# circuit.net
KiCad netlist of a schematic drawn in EAGLE
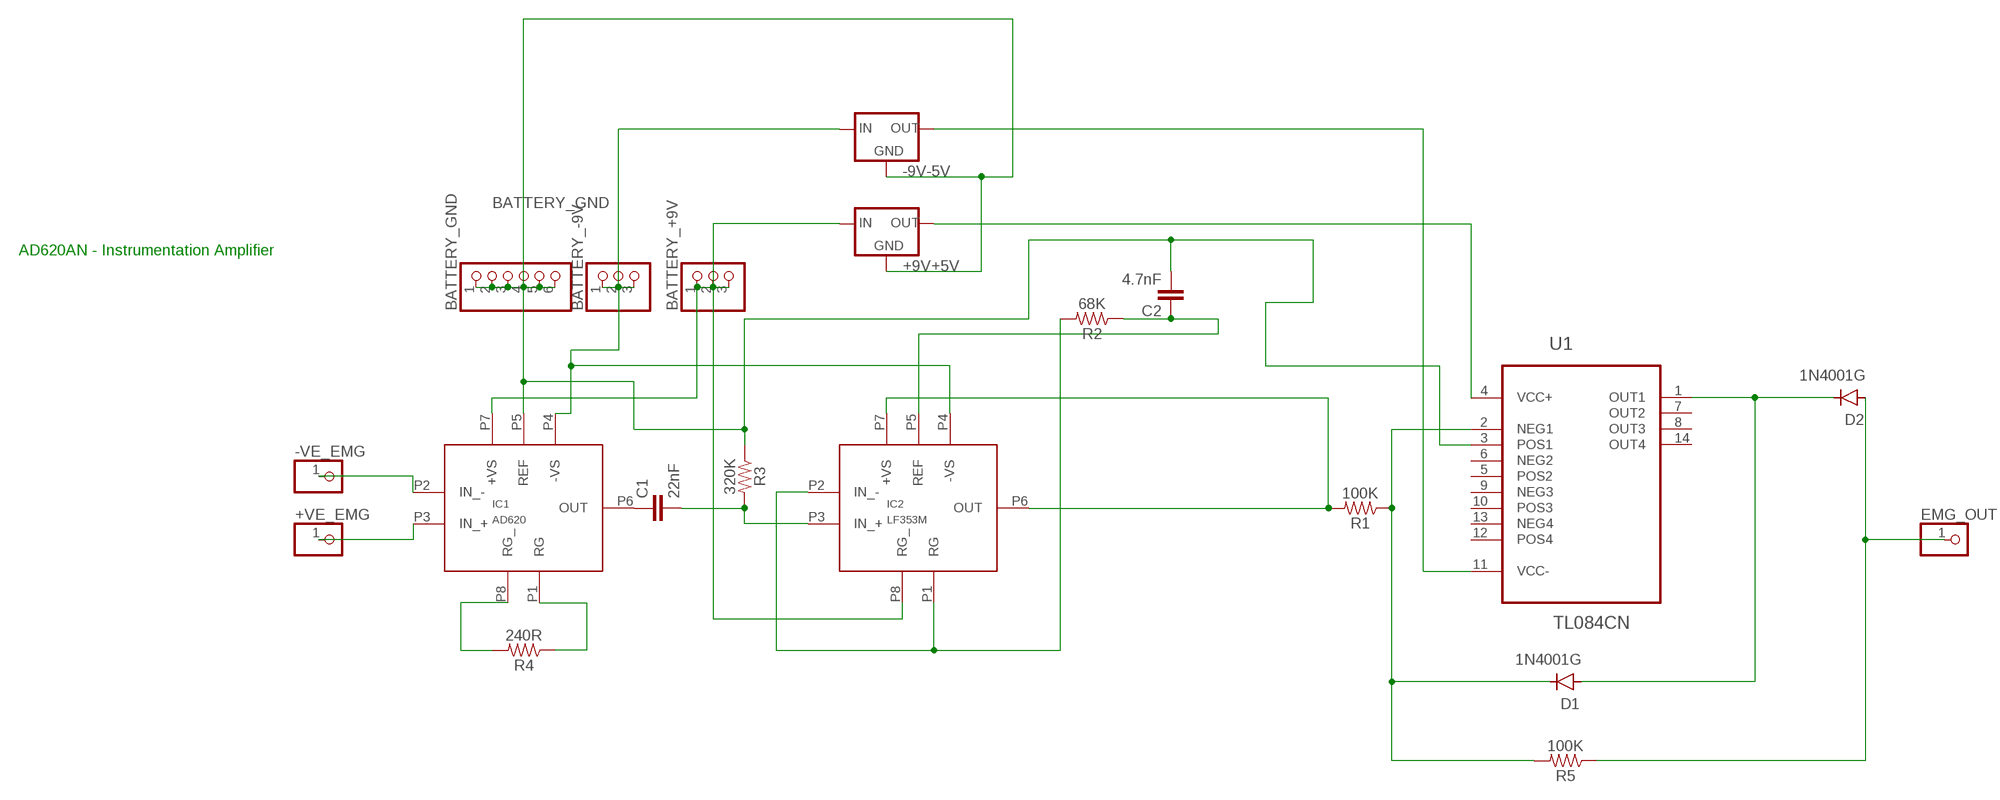
[diagram p0: schematic, sheet 1]

(export (version "E")
  (design (tool "Eeschema 10.0.6"))
  (components
    (comp (ref "+9V+5V")
      (value "78XXL")
      (footprint "eagle-import:78XXL")
      (libsource (lib "eagle-import") (part "78XXL"))
    )
    (comp (ref "+VE_EMG")
      (value "PINHD-1X1")
      (footprint "eagle-import:1X01")
      (libsource (lib "eagle-import") (part "PINHD-1X1"))
    )
    (comp (ref "-9V-5V")
      (value "78XXL")
      (footprint "eagle-import:78XXL")
      (libsource (lib "eagle-import") (part "78XXL"))
    )
    (comp (ref "-VE_EMG")
      (value "PINHD-1X1")
      (footprint "eagle-import:1X01")
      (libsource (lib "eagle-import") (part "PINHD-1X1"))
    )
    (comp (ref "BATTERY_+9V")
      (value "PINHD-1X3")
      (footprint "eagle-import:1X03")
      (libsource (lib "eagle-import") (part "PINHD-1X3"))
    )
    (comp (ref "BATTERY_-9V")
      (value "PINHD-1X3")
      (footprint "eagle-import:1X03")
      (libsource (lib "eagle-import") (part "PINHD-1X3"))
    )
    (comp (ref "BATTERY_GND")
      (value "PINHD-1X6")
      (footprint "eagle-import:1X06")
      (libsource (lib "eagle-import") (part "PINHD-1X6"))
    )
    (comp (ref "C1")
      (value "22nF")
      (footprint "eagle-import:CAP-PTH-10MM")
      (libsource (lib "eagle-import") (part "10NF-PTH-10MM-10000V-1-%"))
    )
    (comp (ref "C2")
      (value "4.7nF")
      (footprint "eagle-import:CAP-PTH-10MM")
      (libsource (lib "eagle-import") (part "10NF-PTH-10MM-10000V-1-%"))
    )
    (comp (ref "D1")
      (value "1N4001G")
      (footprint "eagle-import:DO-41")
      (fields
        (field (name "DIGIKEY_PART_NUMBER") "1N4004MSCT-ND")
        (field (name "MANUFACTURER") "Micro Commercial Co")
        (field (name "MPN") "1N4004")
        (field (name "CREATED_BY") "PCBLayout.com")
      )
      (libsource (lib "eagle-import") (part "1N4004"))
    )
    (comp (ref "D2")
      (value "1N4001G")
      (footprint "eagle-import:DO-41")
      (fields
        (field (name "DIGIKEY_PART_NUMBER") "1N4004MSCT-ND")
        (field (name "MANUFACTURER") "Micro Commercial Co")
        (field (name "MPN") "1N4004")
        (field (name "CREATED_BY") "PCBLayout.com")
      )
      (libsource (lib "eagle-import") (part "1N4004"))
    )
    (comp (ref "EMG_OUT")
      (value "PINHD-1X1")
      (footprint "eagle-import:1X01")
      (libsource (lib "eagle-import") (part "PINHD-1X1"))
    )
    (comp (ref "IC1")
      (value "AD620")
      (footprint "eagle-import:DIL8")
      (libsource (lib "eagle-import") (part "AD620"))
    )
    (comp (ref "IC2")
      (value "LF353M")
      (footprint "eagle-import:DIL8")
      (libsource (lib "eagle-import") (part "AD620"))
    )
    (comp (ref "R1")
      (value "100K")
      (footprint "eagle-import:AXIAL-0.3")
      (libsource (lib "eagle-import") (part "10MOHM-HORIZ-1/4W-5%"))
    )
    (comp (ref "R2")
      (value "68K")
      (footprint "eagle-import:AXIAL-0.3")
      (libsource (lib "eagle-import") (part "10MOHM-HORIZ-1/4W-5%"))
    )
    (comp (ref "R3")
      (value "320K")
      (footprint "eagle-import:AXIAL-0.3")
      (libsource (lib "eagle-import") (part "10MOHM-HORIZ-1/4W-5%"))
    )
    (comp (ref "R4")
      (value "240R")
      (footprint "eagle-import:AXIAL-0.3")
      (libsource (lib "eagle-import") (part "10MOHM-HORIZ-1/4W-5%"))
    )
    (comp (ref "R5")
      (value "100K")
      (footprint "eagle-import:AXIAL-0.3")
      (libsource (lib "eagle-import") (part "10MOHM-HORIZ-1/4W-5%"))
    )
    (comp (ref "U1")
      (value "TL084CN")
      (footprint "eagle-import:DIP254P762X510-14")
      (fields (field (name "MF") "STMicroelectronics"))
      (libsource (lib "eagle-import") (part "TL084CN"))
    )
  )
  (nets
    (net (code "1") (name "/BATTERY_GND") (class "Default")
      (node (ref "+9V+5V") (pin "GND") (pinfunction "GND_GND") (pintype "input"))
      (node (ref "-9V-5V") (pin "GND") (pinfunction "GND_GND") (pintype "input"))
      (node (ref "BATTERY_GND") (pin "1") (pinfunction "1_1") (pintype "passive"))
      (node (ref "BATTERY_GND") (pin "2") (pinfunction "2_2") (pintype "passive"))
      (node (ref "BATTERY_GND") (pin "3") (pinfunction "3_3") (pintype "passive"))
      (node (ref "BATTERY_GND") (pin "4") (pinfunction "4_4") (pintype "passive"))
      (node (ref "BATTERY_GND") (pin "5") (pinfunction "5_5") (pintype "passive"))
      (node (ref "BATTERY_GND") (pin "6") (pinfunction "6_6") (pintype "passive"))
      (node (ref "C2") (pin "2") (pinfunction "2_2") (pintype "passive"))
      (node (ref "IC1") (pin "P5") (pinfunction "REF_P5") (pintype "power_in"))
      (node (ref "R3") (pin "P$1") (pinfunction "1_P$1") (pintype "passive"))
      (node (ref "U1") (pin "3") (pinfunction "POS1_3") (pintype "input"))
    )
    (net (code "2") (name "Net-(IC1-+VS)") (class "Default")
      (node (ref "+9V+5V") (pin "IN") (pinfunction "IN_IN") (pintype "input"))
      (node (ref "BATTERY_+9V") (pin "1") (pinfunction "1_1") (pintype "passive"))
      (node (ref "BATTERY_+9V") (pin "2") (pinfunction "2_2") (pintype "passive"))
      (node (ref "BATTERY_+9V") (pin "3") (pinfunction "3_3") (pintype "passive"))
      (node (ref "IC1") (pin "P7") (pinfunction "+VS_P7") (pintype "power_in"))
      (node (ref "IC2") (pin "P8") (pinfunction "RG__P8") (pintype "input"))
    )
    (net (code "3") (name "Net-(IC1--VS)") (class "Default")
      (node (ref "-9V-5V") (pin "IN") (pinfunction "IN_IN") (pintype "input"))
      (node (ref "BATTERY_-9V") (pin "1") (pinfunction "1_1") (pintype "passive"))
      (node (ref "BATTERY_-9V") (pin "2") (pinfunction "2_2") (pintype "passive"))
      (node (ref "BATTERY_-9V") (pin "3") (pinfunction "3_3") (pintype "passive"))
      (node (ref "IC1") (pin "P4") (pinfunction "-VS_P4") (pintype "power_in"))
      (node (ref "IC2") (pin "P4") (pinfunction "-VS_P4") (pintype "power_in"))
    )
    (net (code "4") (name "Net-(IC1-IN_+)") (class "Default")
      (node (ref "+VE_EMG") (pin "1") (pinfunction "1_1") (pintype "passive"))
      (node (ref "IC1") (pin "P3") (pinfunction "IN_+_P3") (pintype "input"))
    )
    (net (code "5") (name "Net-(IC1-IN_-)") (class "Default")
      (node (ref "-VE_EMG") (pin "1") (pinfunction "1_1") (pintype "passive"))
      (node (ref "IC1") (pin "P2") (pinfunction "IN_-_P2") (pintype "input"))
    )
    (net (code "6") (name "Net-(IC1-OUT)") (class "Default")
      (node (ref "C1") (pin "1") (pinfunction "1_1") (pintype "passive"))
      (node (ref "IC1") (pin "P6") (pinfunction "OUT_P6") (pintype "output"))
    )
    (net (code "7") (name "Net-(IC1-RG)") (class "Default")
      (node (ref "IC1") (pin "P1") (pinfunction "RG_P1") (pintype "input"))
      (node (ref "R4") (pin "P$1") (pinfunction "1_P$1") (pintype "passive"))
    )
    (net (code "8") (name "Net-(IC1-RG_)") (class "Default")
      (node (ref "IC1") (pin "P8") (pinfunction "RG__P8") (pintype "input"))
      (node (ref "R4") (pin "P$2") (pinfunction "2_P$2") (pintype "passive"))
    )
    (net (code "9") (name "Net-(IC2-+VS)") (class "Default")
      (node (ref "IC2") (pin "P6") (pinfunction "OUT_P6") (pintype "output"))
      (node (ref "IC2") (pin "P7") (pinfunction "+VS_P7") (pintype "power_in"))
      (node (ref "R1") (pin "P$2") (pinfunction "2_P$2") (pintype "passive"))
    )
    (net (code "10") (name "Net-(IC2-IN_+)") (class "Default")
      (node (ref "C1") (pin "2") (pinfunction "2_2") (pintype "passive"))
      (node (ref "IC2") (pin "P3") (pinfunction "IN_+_P3") (pintype "input"))
      (node (ref "R3") (pin "P$2") (pinfunction "2_P$2") (pintype "passive"))
    )
    (net (code "11") (name "Net-(IC2-IN_-)") (class "Default")
      (node (ref "IC2") (pin "P1") (pinfunction "RG_P1") (pintype "input"))
      (node (ref "IC2") (pin "P2") (pinfunction "IN_-_P2") (pintype "input"))
      (node (ref "R2") (pin "P$2") (pinfunction "2_P$2") (pintype "passive"))
    )
    (net (code "12") (name "Net-(IC2-REF)") (class "Default")
      (node (ref "C2") (pin "1") (pinfunction "1_1") (pintype "passive"))
      (node (ref "IC2") (pin "P5") (pinfunction "REF_P5") (pintype "power_in"))
      (node (ref "R2") (pin "P$1") (pinfunction "1_P$1") (pintype "passive"))
    )
    (net (code "13") (name "Net-(R1-1)") (class "Default")
      (node (ref "D1") (pin "C") (pinfunction "C_C") (pintype "passive"))
      (node (ref "R1") (pin "P$1") (pinfunction "1_P$1") (pintype "passive"))
      (node (ref "R5") (pin "P$2") (pinfunction "2_P$2") (pintype "passive"))
      (node (ref "U1") (pin "2") (pinfunction "NEG1_2") (pintype "input"))
    )
    (net (code "14") (name "Net-(R5-1)") (class "Default")
      (node (ref "D2") (pin "A") (pinfunction "A_A") (pintype "passive"))
      (node (ref "EMG_OUT") (pin "1") (pinfunction "1_1") (pintype "passive"))
      (node (ref "R5") (pin "P$1") (pinfunction "1_P$1") (pintype "passive"))
    )
    (net (code "15") (name "Net-(U1-OUT1)") (class "Default")
      (node (ref "D1") (pin "A") (pinfunction "A_A") (pintype "passive"))
      (node (ref "D2") (pin "C") (pinfunction "C_C") (pintype "passive"))
      (node (ref "U1") (pin "1") (pinfunction "OUT1_1") (pintype "output"))
    )
    (net (code "16") (name "Net-(U1-VCC+)") (class "Default")
      (node (ref "+9V+5V") (pin "OUT") (pinfunction "OUT_OUT") (pintype "passive"))
      (node (ref "U1") (pin "4") (pinfunction "VCC+_4") (pintype "power_in"))
    )
    (net (code "17") (name "Net-(U1-VCC-)") (class "Default")
      (node (ref "-9V-5V") (pin "OUT") (pinfunction "OUT_OUT") (pintype "passive"))
      (node (ref "U1") (pin "11") (pinfunction "VCC-_11") (pintype "power_in"))
    )
    (net (code "18") (name "unconnected-(U1-NEG2-Pad6)") (class "Default")
      (node (ref "U1") (pin "6") (pinfunction "NEG2_6") (pintype "input"))
    )
    (net (code "19") (name "unconnected-(U1-NEG3-Pad9)") (class "Default")
      (node (ref "U1") (pin "9") (pinfunction "NEG3_9") (pintype "input"))
    )
    (net (code "20") (name "unconnected-(U1-NEG4-Pad13)") (class "Default")
      (node (ref "U1") (pin "13") (pinfunction "NEG4_13") (pintype "input"))
    )
    (net (code "21") (name "unconnected-(U1-OUT2-Pad7)") (class "Default")
      (node (ref "U1") (pin "7") (pinfunction "OUT2_7") (pintype "output"))
    )
    (net (code "22") (name "unconnected-(U1-OUT3-Pad8)") (class "Default")
      (node (ref "U1") (pin "8") (pinfunction "OUT3_8") (pintype "output"))
    )
    (net (code "23") (name "unconnected-(U1-OUT4-Pad14)") (class "Default")
      (node (ref "U1") (pin "14") (pinfunction "OUT4_14") (pintype "output"))
    )
    (net (code "24") (name "unconnected-(U1-POS2-Pad5)") (class "Default")
      (node (ref "U1") (pin "5") (pinfunction "POS2_5") (pintype "input"))
    )
    (net (code "25") (name "unconnected-(U1-POS3-Pad10)") (class "Default")
      (node (ref "U1") (pin "10") (pinfunction "POS3_10") (pintype "input"))
    )
    (net (code "26") (name "unconnected-(U1-POS4-Pad12)") (class "Default")
      (node (ref "U1") (pin "12") (pinfunction "POS4_12") (pintype "input"))
    )
  )
)
